# pcb_telemetria_wide.net
KiCad netlist of a schematic drawn in EAGLE
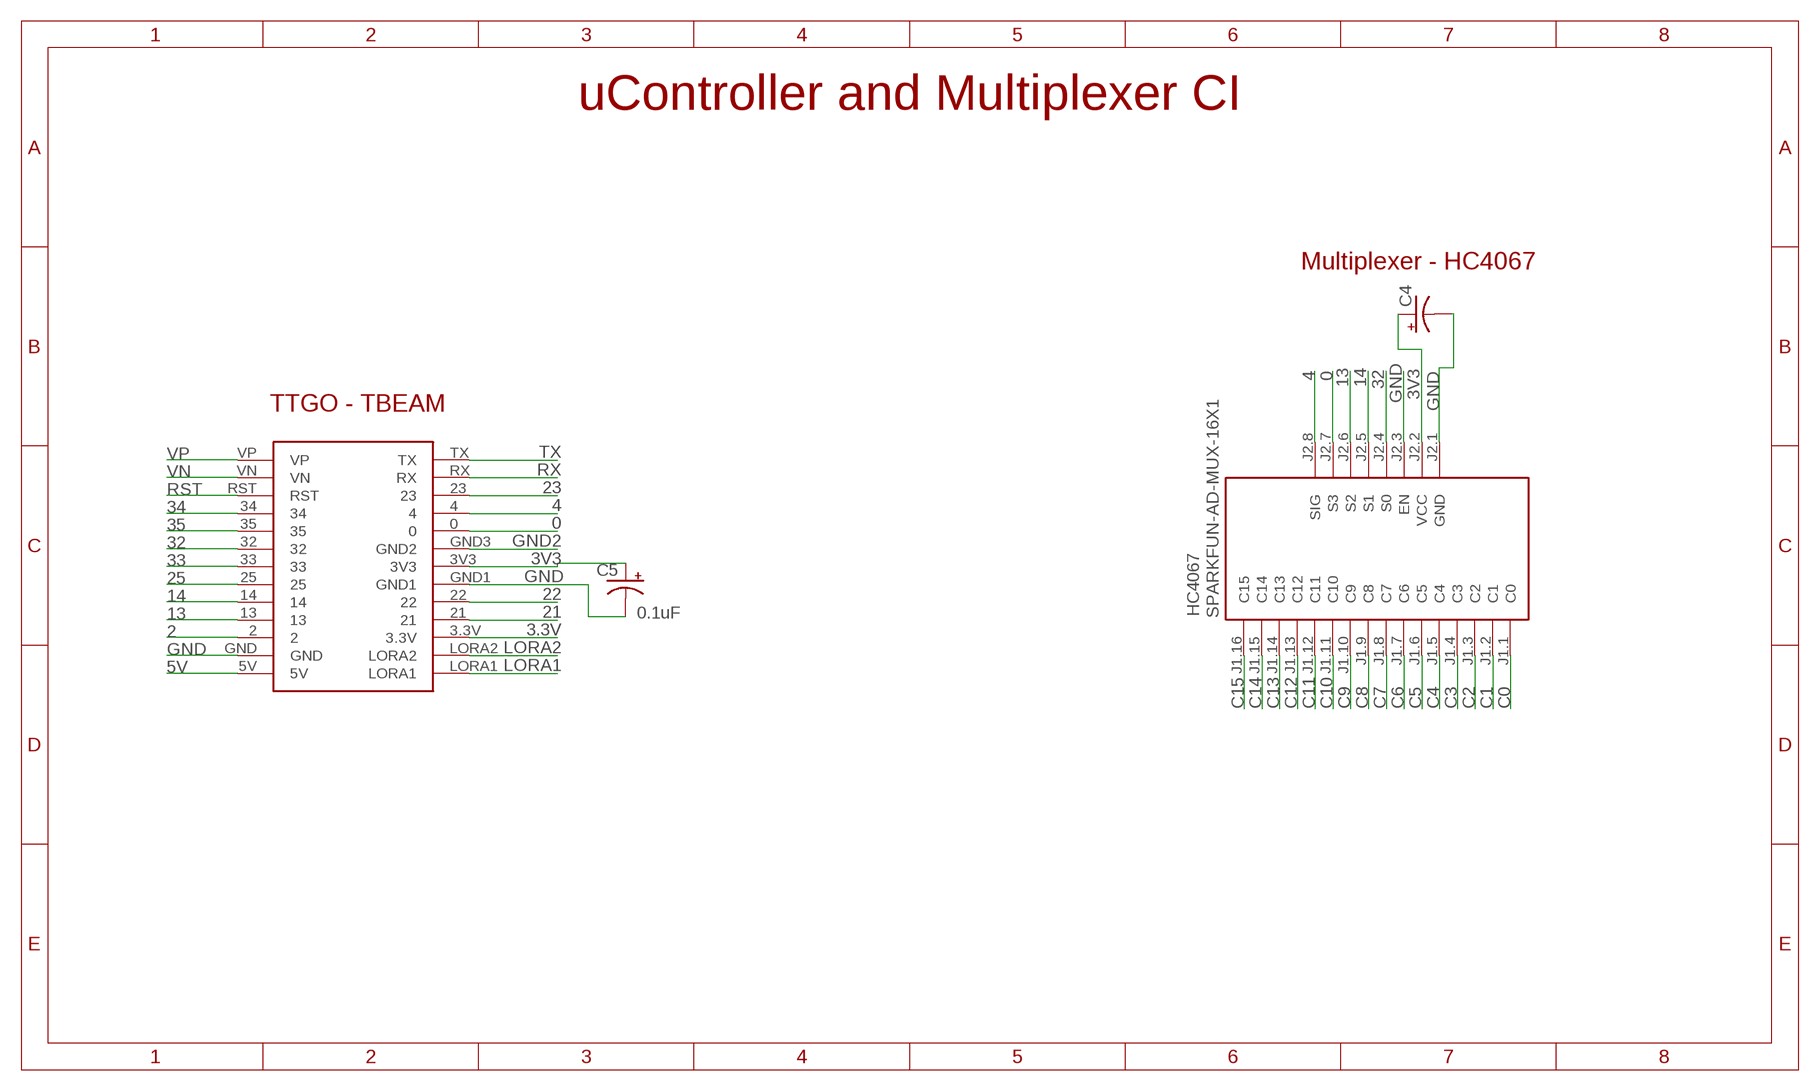
[diagram p0: schematic, sheet 1]
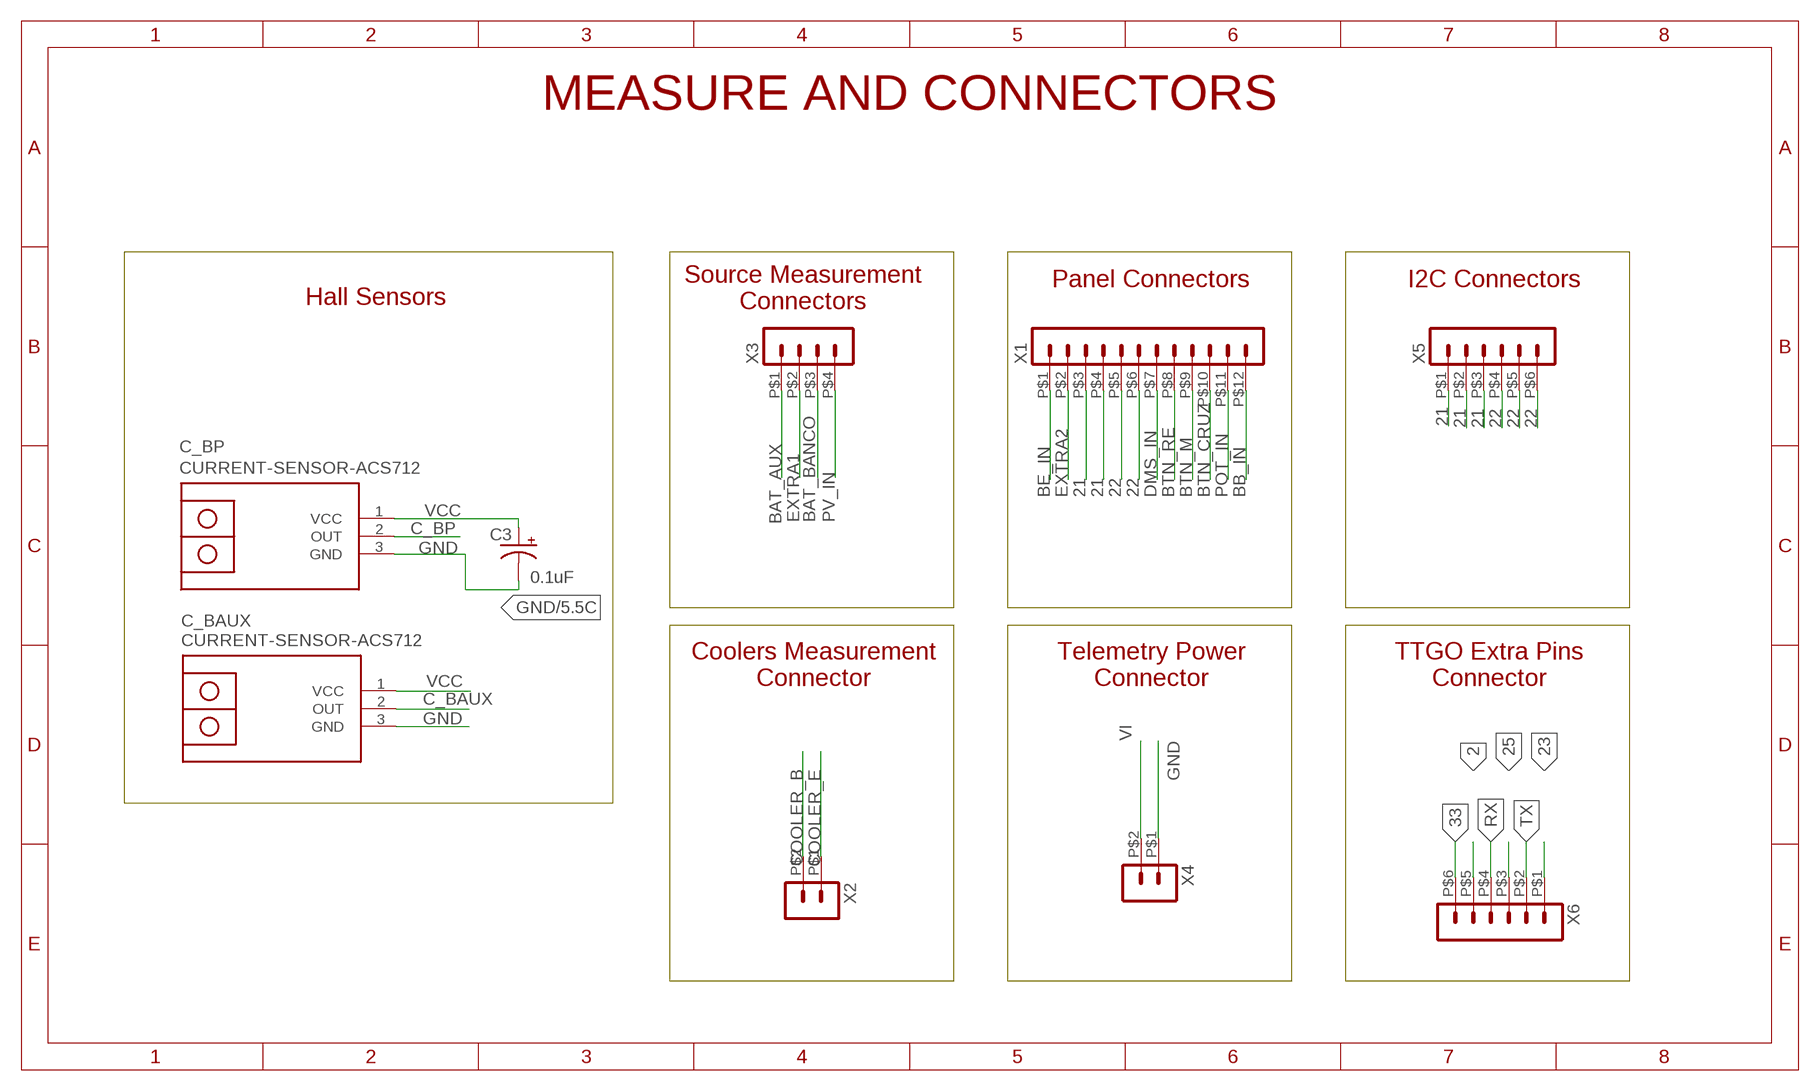
[diagram p1: schematic, sheet 2]
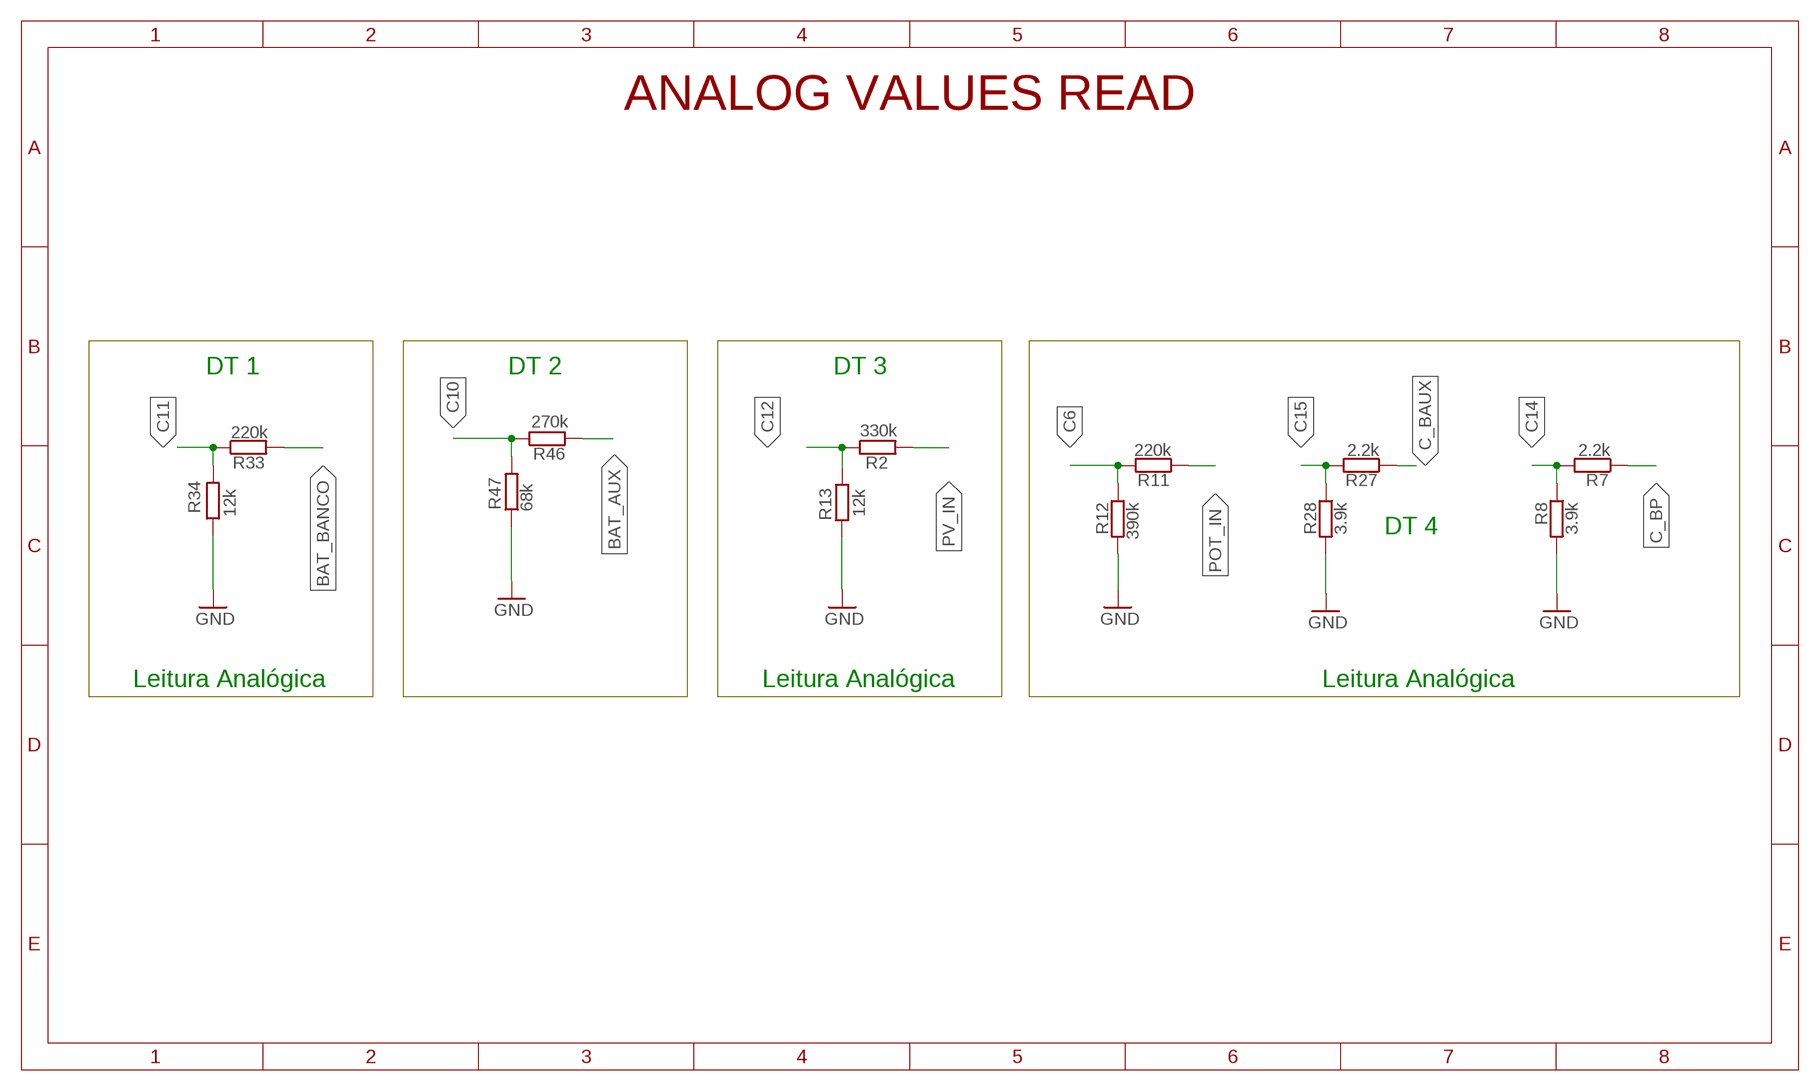
[diagram p2: schematic, sheet 3]
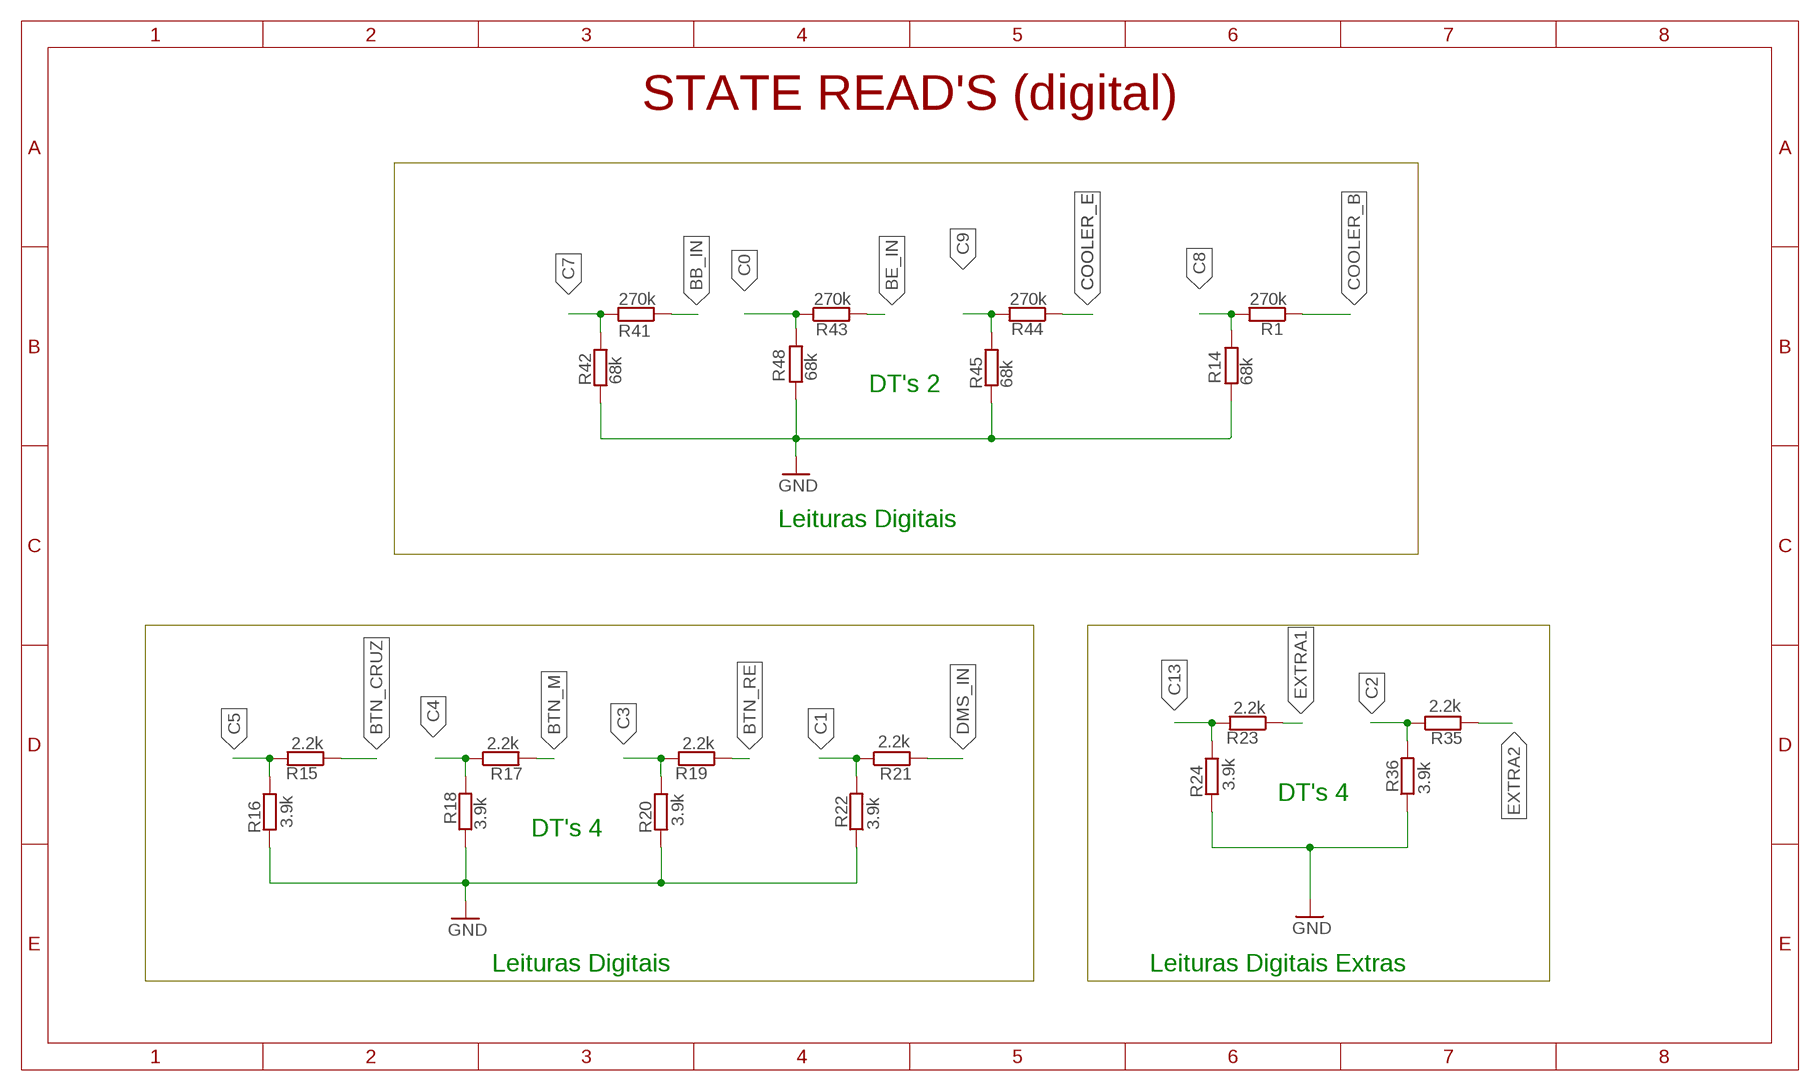
[diagram p3: schematic, sheet 4]
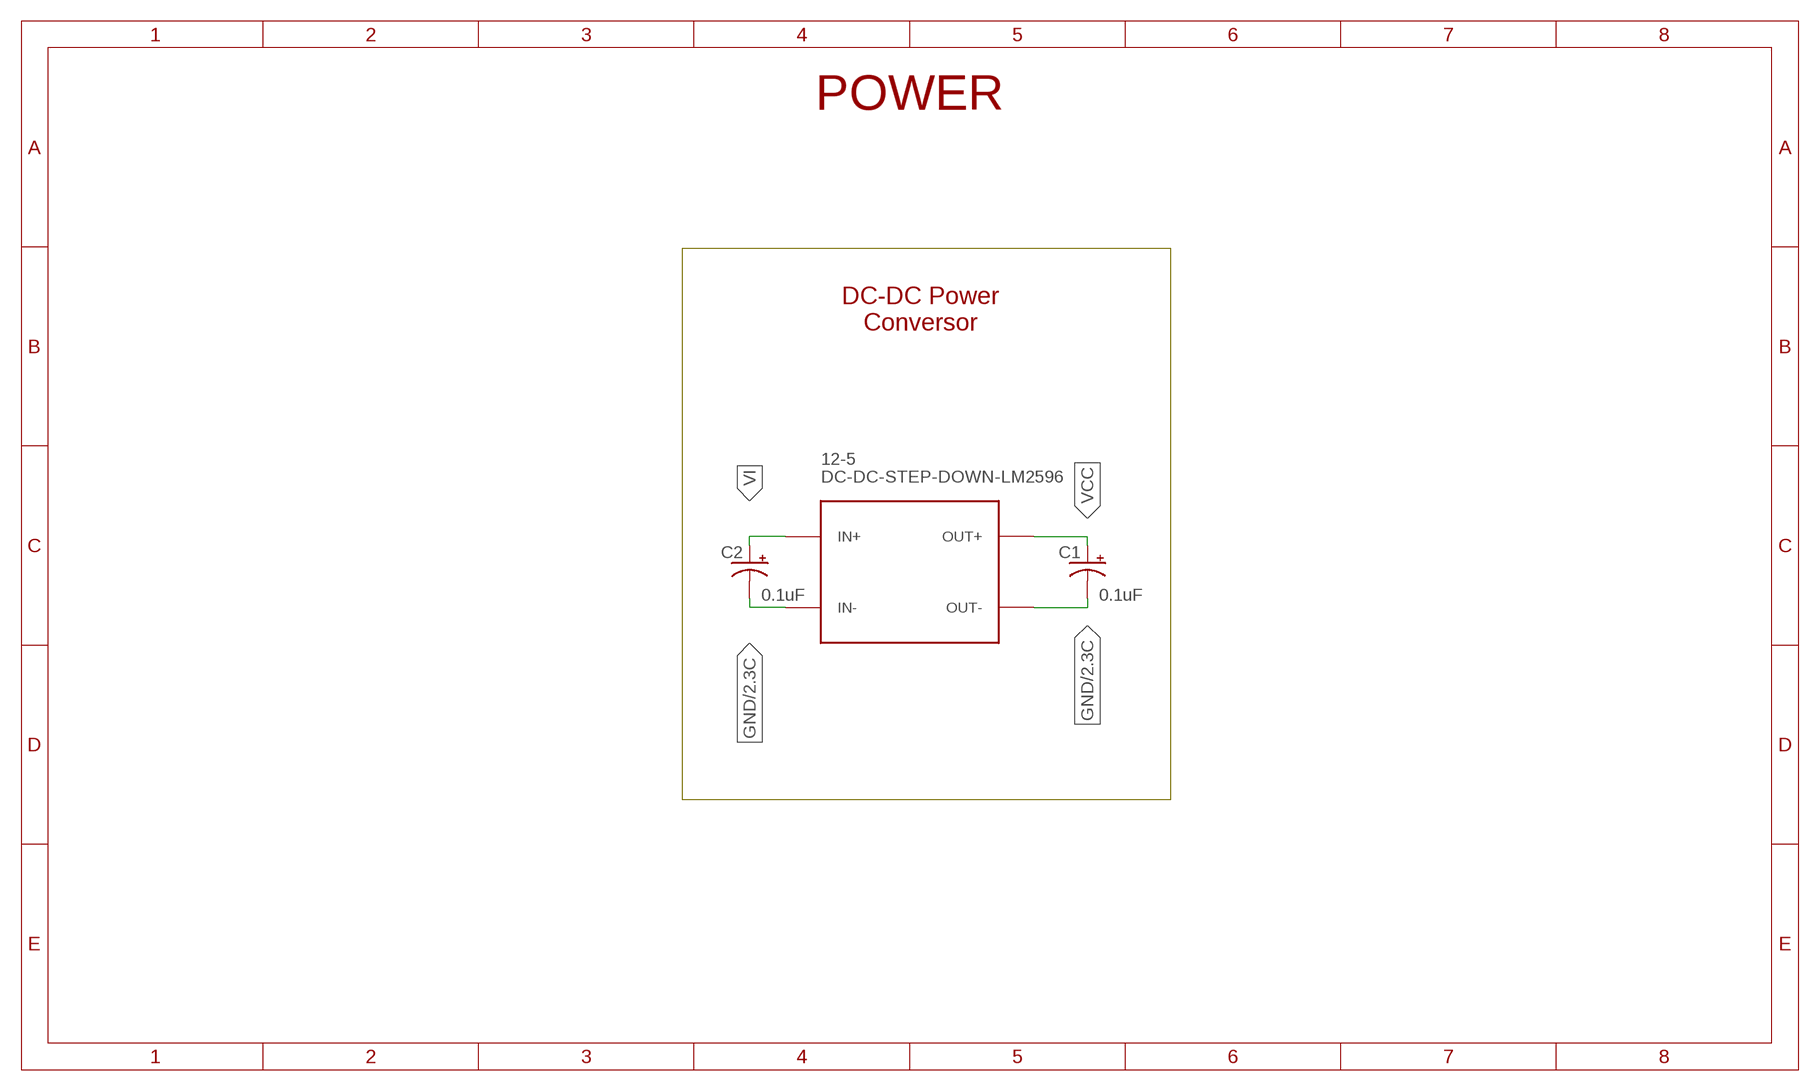
[diagram p4: schematic, sheet 5]

(export (version "E")
  (design (tool "Eeschema 10.0.6"))
  (components
    (comp (ref "12-5")
      (value "DC-DC-STEP-DOWN-LM2596")
      (footprint "eagle-import:DC-DC-STEP-DOWN-LM2596")
      (libsource (lib "eagle-import") (part "DC-DC-STEP-DOWN-LM2596"))
    )
    (comp (ref "C1")
      (value "0.1uF")
      (footprint "eagle-import:E5-5")
      (libsource (lib "eagle-import") (part "CPOL-USE5-5"))
    )
    (comp (ref "C2")
      (value "0.1uF")
      (footprint "eagle-import:E5-5")
      (libsource (lib "eagle-import") (part "CPOL-USE5-5"))
    )
    (comp (ref "R1")
      (value "270k")
      (footprint "eagle-import:0204_7")
      (libsource (lib "eagle-import") (part "R-EU_0204/7"))
    )
    (comp (ref "R14")
      (value "68k")
      (footprint "eagle-import:0204_7")
      (libsource (lib "eagle-import") (part "R-EU_0204/7"))
    )
    (comp (ref "R15")
      (value "2.2k")
      (footprint "eagle-import:0204_7")
      (libsource (lib "eagle-import") (part "R-EU_0204/7"))
    )
    (comp (ref "R16")
      (value "3.9k")
      (footprint "eagle-import:0204_7")
      (libsource (lib "eagle-import") (part "R-EU_0204/7"))
    )
    (comp (ref "R17")
      (value "2.2k")
      (footprint "eagle-import:0204_7")
      (libsource (lib "eagle-import") (part "R-EU_0204/7"))
    )
    (comp (ref "R18")
      (value "3.9k")
      (footprint "eagle-import:0204_7")
      (libsource (lib "eagle-import") (part "R-EU_0204/7"))
    )
    (comp (ref "R19")
      (value "2.2k")
      (footprint "eagle-import:0204_7")
      (libsource (lib "eagle-import") (part "R-EU_0204/7"))
    )
    (comp (ref "R20")
      (value "3.9k")
      (footprint "eagle-import:0204_7")
      (libsource (lib "eagle-import") (part "R-EU_0204/7"))
    )
    (comp (ref "R21")
      (value "2.2k")
      (footprint "eagle-import:0204_7")
      (libsource (lib "eagle-import") (part "R-EU_0204/7"))
    )
    (comp (ref "R22")
      (value "3.9k")
      (footprint "eagle-import:0204_7")
      (libsource (lib "eagle-import") (part "R-EU_0204/7"))
    )
    (comp (ref "R23")
      (value "2.2k")
      (footprint "eagle-import:0204_7")
      (libsource (lib "eagle-import") (part "R-EU_0204/7"))
    )
    (comp (ref "R24")
      (value "3.9k")
      (footprint "eagle-import:0204_7")
      (libsource (lib "eagle-import") (part "R-EU_0204/7"))
    )
    (comp (ref "R35")
      (value "2.2k")
      (footprint "eagle-import:0204_7")
      (libsource (lib "eagle-import") (part "R-EU_0204/7"))
    )
    (comp (ref "R36")
      (value "3.9k")
      (footprint "eagle-import:0204_7")
      (libsource (lib "eagle-import") (part "R-EU_0204/7"))
    )
    (comp (ref "R41")
      (value "270k")
      (footprint "eagle-import:0204_7")
      (libsource (lib "eagle-import") (part "R-EU_0204/7"))
    )
    (comp (ref "R42")
      (value "68k")
      (footprint "eagle-import:0204_7")
      (libsource (lib "eagle-import") (part "R-EU_0204/7"))
    )
    (comp (ref "R43")
      (value "270k")
      (footprint "eagle-import:0204_7")
      (libsource (lib "eagle-import") (part "R-EU_0204/7"))
    )
    (comp (ref "R44")
      (value "270k")
      (footprint "eagle-import:0204_7")
      (libsource (lib "eagle-import") (part "R-EU_0204/7"))
    )
    (comp (ref "R45")
      (value "68k")
      (footprint "eagle-import:0204_7")
      (libsource (lib "eagle-import") (part "R-EU_0204/7"))
    )
    (comp (ref "R48")
      (value "68k")
      (footprint "eagle-import:0204_7")
      (libsource (lib "eagle-import") (part "R-EU_0204/7"))
    )
    (comp (ref "C4")
      (value "CPOL-USE5-5")
      (footprint "eagle-import:E5-5")
      (libsource (lib "eagle-import") (part "CPOL-USE5-5"))
    )
    (comp (ref "C5")
      (value "0.1uF")
      (footprint "eagle-import:E5-5")
      (libsource (lib "eagle-import") (part "CPOL-USE5-5"))
    )
    (comp (ref "HC4067")
      (value "SPARKFUN-AD-MUX-16X1")
      (footprint "eagle-import:SPARKFUN-AD-MUX-16X1")
      (libsource (lib "eagle-import") (part "SPARKFUN-AD-MUX-16X1"))
    )
    (comp (ref "U$1")
      (value "TTGOBEAM")
      (footprint "eagle-import:TTGOBEAM")
      (libsource (lib "eagle-import") (part "TTGOBEAM"))
    )
    (comp (ref "R2")
      (value "330k")
      (footprint "eagle-import:0204_7")
      (libsource (lib "eagle-import") (part "R-EU_0204/7"))
    )
    (comp (ref "R7")
      (value "2.2k")
      (footprint "eagle-import:0204_7")
      (libsource (lib "eagle-import") (part "R-EU_0204/7"))
    )
    (comp (ref "R8")
      (value "3.9k")
      (footprint "eagle-import:0204_7")
      (libsource (lib "eagle-import") (part "R-EU_0204/7"))
    )
    (comp (ref "R11")
      (value "220k")
      (footprint "eagle-import:0204_7")
      (libsource (lib "eagle-import") (part "R-EU_0204/7"))
    )
    (comp (ref "R12")
      (value "390k")
      (footprint "eagle-import:0204_7")
      (libsource (lib "eagle-import") (part "R-EU_0204/7"))
    )
    (comp (ref "R13")
      (value "12k")
      (footprint "eagle-import:0204_7")
      (libsource (lib "eagle-import") (part "R-EU_0204/7"))
    )
    (comp (ref "R27")
      (value "2.2k")
      (footprint "eagle-import:0204_7")
      (libsource (lib "eagle-import") (part "R-EU_0204/7"))
    )
    (comp (ref "R28")
      (value "3.9k")
      (footprint "eagle-import:0204_7")
      (libsource (lib "eagle-import") (part "R-EU_0204/7"))
    )
    (comp (ref "R33")
      (value "220k")
      (footprint "eagle-import:0204_7")
      (libsource (lib "eagle-import") (part "R-EU_0204/7"))
    )
    (comp (ref "R34")
      (value "12k")
      (footprint "eagle-import:0204_7")
      (libsource (lib "eagle-import") (part "R-EU_0204/7"))
    )
    (comp (ref "R46")
      (value "270k")
      (footprint "eagle-import:0204_7")
      (libsource (lib "eagle-import") (part "R-EU_0204/7"))
    )
    (comp (ref "R47")
      (value "68k")
      (footprint "eagle-import:0204_7")
      (libsource (lib "eagle-import") (part "R-EU_0204/7"))
    )
    (comp (ref "C3")
      (value "0.1uF")
      (footprint "eagle-import:E5-5")
      (libsource (lib "eagle-import") (part "CPOL-USE5-5"))
    )
    (comp (ref "C_BAUX")
      (value "CURRENT-SENSOR-ACS712")
      (footprint "eagle-import:CURRENT-SENSOR-ACS712")
      (libsource (lib "eagle-import") (part "CURRENT-SENSOR-ACS712"))
    )
    (comp (ref "C_BP")
      (value "CURRENT-SENSOR-ACS712")
      (footprint "eagle-import:CURRENT-SENSOR-ACS712")
      (libsource (lib "eagle-import") (part "CURRENT-SENSOR-ACS712"))
    )
    (comp (ref "X1")
      (value "HEADER_POS12_43045-1212")
      (footprint "eagle-import:43045-1212")
      (libsource (lib "eagle-import") (part "HEADER_POS12_?43045-1212"))
    )
    (comp (ref "X2")
      (value "HEADER_POS2_43045-0212")
      (footprint "eagle-import:43045-0212")
      (libsource (lib "eagle-import") (part "HEADER_POS2_?43045-0212"))
    )
    (comp (ref "X3")
      (value "HEADER_POS4_43045-0412")
      (footprint "eagle-import:43045-0412")
      (libsource (lib "eagle-import") (part "HEADER_POS4_?43045-0412"))
    )
    (comp (ref "X4")
      (value "HEADER_POS2_43045-0212")
      (footprint "eagle-import:43045-0212")
      (libsource (lib "eagle-import") (part "HEADER_POS2_?43045-0212"))
    )
    (comp (ref "X5")
      (value "HEADER_POS6_43045-0612")
      (footprint "eagle-import:43045-0612")
      (libsource (lib "eagle-import") (part "HEADER_POS6_?43045-0612"))
    )
    (comp (ref "X6")
      (value "HEADER_POS6_43045-0612")
      (footprint "eagle-import:43045-0612")
      (libsource (lib "eagle-import") (part "HEADER_POS6_?43045-0612"))
    )
  )
  (nets
    (net (code "1") (name "0") (class "Default")
      (node (ref "HC4067") (pin "J2.7") (pinfunction "S3_J2.7") (pintype "bidirectional"))
      (node (ref "U$1") (pin "0") (pinfunction "0_0") (pintype "bidirectional"))
    )
    (net (code "2") (name "2") (class "Default")
      (node (ref "U$1") (pin "2") (pinfunction "2_2") (pintype "bidirectional"))
      (node (ref "X6") (pin "P$5") (pinfunction "5_P$5") (pintype "passive"))
    )
    (net (code "3") (name "3.3V") (class "Default")
      (node (ref "U$1") (pin "3.3V") (pinfunction "3.3V_3.3V") (pintype "bidirectional"))
    )
    (net (code "4") (name "3V3") (class "Default")
      (node (ref "C4") (pin "+") (pinfunction "+_+") (pintype "passive"))
      (node (ref "C5") (pin "+") (pinfunction "+_+") (pintype "passive"))
      (node (ref "HC4067") (pin "J2.2") (pinfunction "VCC_J2.2") (pintype "power_in"))
      (node (ref "U$1") (pin "3V3") (pinfunction "3V3_3V3") (pintype "bidirectional"))
    )
    (net (code "5") (name "4") (class "Default")
      (node (ref "HC4067") (pin "J2.8") (pinfunction "SIG_J2.8") (pintype "bidirectional"))
      (node (ref "U$1") (pin "4") (pinfunction "4_4") (pintype "bidirectional"))
    )
    (net (code "6") (name "5V") (class "Default")
      (node (ref "U$1") (pin "5V") (pinfunction "5V_5V") (pintype "bidirectional"))
    )
    (net (code "7") (name "13") (class "Default")
      (node (ref "HC4067") (pin "J2.6") (pinfunction "S2_J2.6") (pintype "bidirectional"))
      (node (ref "U$1") (pin "13") (pinfunction "13_13") (pintype "bidirectional"))
    )
    (net (code "8") (name "14") (class "Default")
      (node (ref "HC4067") (pin "J2.5") (pinfunction "S1_J2.5") (pintype "bidirectional"))
      (node (ref "U$1") (pin "14") (pinfunction "14_14") (pintype "bidirectional"))
    )
    (net (code "9") (name "21") (class "Default")
      (node (ref "U$1") (pin "21") (pinfunction "21_21") (pintype "bidirectional"))
      (node (ref "X1") (pin "P$3") (pinfunction "3_P$3") (pintype "passive"))
      (node (ref "X1") (pin "P$4") (pinfunction "4_P$4") (pintype "passive"))
      (node (ref "X5") (pin "P$1") (pinfunction "1_P$1") (pintype "passive"))
      (node (ref "X5") (pin "P$2") (pinfunction "2_P$2") (pintype "passive"))
      (node (ref "X5") (pin "P$3") (pinfunction "3_P$3") (pintype "passive"))
    )
    (net (code "10") (name "22") (class "Default")
      (node (ref "U$1") (pin "22") (pinfunction "22_22") (pintype "bidirectional"))
      (node (ref "X1") (pin "P$5") (pinfunction "5_P$5") (pintype "passive"))
      (node (ref "X1") (pin "P$6") (pinfunction "6_P$6") (pintype "passive"))
      (node (ref "X5") (pin "P$4") (pinfunction "4_P$4") (pintype "passive"))
      (node (ref "X5") (pin "P$5") (pinfunction "5_P$5") (pintype "passive"))
      (node (ref "X5") (pin "P$6") (pinfunction "6_P$6") (pintype "passive"))
    )
    (net (code "11") (name "23") (class "Default")
      (node (ref "U$1") (pin "23") (pinfunction "23_23") (pintype "bidirectional"))
      (node (ref "X6") (pin "P$1") (pinfunction "1_P$1") (pintype "passive"))
    )
    (net (code "12") (name "25") (class "Default")
      (node (ref "U$1") (pin "25") (pinfunction "25_25") (pintype "bidirectional"))
      (node (ref "X6") (pin "P$3") (pinfunction "3_P$3") (pintype "passive"))
    )
    (net (code "13") (name "32") (class "Default")
      (node (ref "HC4067") (pin "J2.4") (pinfunction "S0_J2.4") (pintype "bidirectional"))
      (node (ref "U$1") (pin "32") (pinfunction "32_32") (pintype "bidirectional"))
    )
    (net (code "14") (name "33") (class "Default")
      (node (ref "U$1") (pin "33") (pinfunction "33_33") (pintype "bidirectional"))
      (node (ref "X6") (pin "P$6") (pinfunction "6_P$6") (pintype "passive"))
    )
    (net (code "15") (name "34") (class "Default")
      (node (ref "U$1") (pin "34") (pinfunction "34_34") (pintype "bidirectional"))
    )
    (net (code "16") (name "35") (class "Default")
      (node (ref "U$1") (pin "35") (pinfunction "35_35") (pintype "bidirectional"))
    )
    (net (code "17") (name "BAT_AUX") (class "Default")
      (node (ref "R46") (pin "2") (pinfunction "2_2") (pintype "passive"))
      (node (ref "X3") (pin "P$1") (pinfunction "1_P$1") (pintype "passive"))
    )
    (net (code "18") (name "BAT_BANCO") (class "Default")
      (node (ref "R33") (pin "2") (pinfunction "2_2") (pintype "passive"))
      (node (ref "X3") (pin "P$3") (pinfunction "3_P$3") (pintype "passive"))
    )
    (net (code "19") (name "BB_IN") (class "Default")
      (node (ref "R41") (pin "1") (pinfunction "1_1") (pintype "passive"))
      (node (ref "X1") (pin "P$12") (pinfunction "12_P$12") (pintype "passive"))
    )
    (net (code "20") (name "BE_IN") (class "Default")
      (node (ref "R43") (pin "2") (pinfunction "2_2") (pintype "passive"))
      (node (ref "X1") (pin "P$1") (pinfunction "1_P$1") (pintype "passive"))
    )
    (net (code "21") (name "BTN_CRUZ") (class "Default")
      (node (ref "R15") (pin "1") (pinfunction "1_1") (pintype "passive"))
      (node (ref "X1") (pin "P$10") (pinfunction "10_P$10") (pintype "passive"))
    )
    (net (code "22") (name "BTN_M") (class "Default")
      (node (ref "R17") (pin "2") (pinfunction "2_2") (pintype "passive"))
      (node (ref "X1") (pin "P$9") (pinfunction "9_P$9") (pintype "passive"))
    )
    (net (code "23") (name "BTN_RE") (class "Default")
      (node (ref "R19") (pin "1") (pinfunction "1_1") (pintype "passive"))
      (node (ref "X1") (pin "P$8") (pinfunction "8_P$8") (pintype "passive"))
    )
    (net (code "24") (name "C0") (class "Default")
      (node (ref "HC4067") (pin "J1.1") (pinfunction "C0_J1.1") (pintype "bidirectional"))
      (node (ref "R43") (pin "1") (pinfunction "1_1") (pintype "passive"))
      (node (ref "R48") (pin "1") (pinfunction "1_1") (pintype "passive"))
    )
    (net (code "25") (name "C1") (class "Default")
      (node (ref "HC4067") (pin "J1.2") (pinfunction "C1_J1.2") (pintype "bidirectional"))
      (node (ref "R21") (pin "1") (pinfunction "1_1") (pintype "passive"))
      (node (ref "R22") (pin "2") (pinfunction "2_2") (pintype "passive"))
    )
    (net (code "26") (name "C2") (class "Default")
      (node (ref "HC4067") (pin "J1.3") (pinfunction "C2_J1.3") (pintype "bidirectional"))
      (node (ref "R35") (pin "1") (pinfunction "1_1") (pintype "passive"))
      (node (ref "R36") (pin "2") (pinfunction "2_2") (pintype "passive"))
    )
    (net (code "27") (name "C3") (class "Default")
      (node (ref "HC4067") (pin "J1.4") (pinfunction "C3_J1.4") (pintype "bidirectional"))
      (node (ref "R19") (pin "2") (pinfunction "2_2") (pintype "passive"))
      (node (ref "R20") (pin "1") (pinfunction "1_1") (pintype "passive"))
    )
    (net (code "28") (name "C4") (class "Default")
      (node (ref "HC4067") (pin "J1.5") (pinfunction "C4_J1.5") (pintype "bidirectional"))
      (node (ref "R17") (pin "1") (pinfunction "1_1") (pintype "passive"))
      (node (ref "R18") (pin "2") (pinfunction "2_2") (pintype "passive"))
    )
    (net (code "29") (name "C5") (class "Default")
      (node (ref "HC4067") (pin "J1.6") (pinfunction "C5_J1.6") (pintype "bidirectional"))
      (node (ref "R15") (pin "2") (pinfunction "2_2") (pintype "passive"))
      (node (ref "R16") (pin "1") (pinfunction "1_1") (pintype "passive"))
    )
    (net (code "30") (name "C6") (class "Default")
      (node (ref "HC4067") (pin "J1.7") (pinfunction "C6_J1.7") (pintype "bidirectional"))
      (node (ref "R11") (pin "2") (pinfunction "2_2") (pintype "passive"))
      (node (ref "R12") (pin "1") (pinfunction "1_1") (pintype "passive"))
    )
    (net (code "31") (name "C7") (class "Default")
      (node (ref "HC4067") (pin "J1.8") (pinfunction "C7_J1.8") (pintype "bidirectional"))
      (node (ref "R41") (pin "2") (pinfunction "2_2") (pintype "passive"))
      (node (ref "R42") (pin "1") (pinfunction "1_1") (pintype "passive"))
    )
    (net (code "32") (name "C8") (class "Default")
      (node (ref "HC4067") (pin "J1.9") (pinfunction "C8_J1.9") (pintype "bidirectional"))
      (node (ref "R1") (pin "2") (pinfunction "2_2") (pintype "passive"))
      (node (ref "R14") (pin "2") (pinfunction "2_2") (pintype "passive"))
    )
    (net (code "33") (name "C9") (class "Default")
      (node (ref "HC4067") (pin "J1.10") (pinfunction "C9_J1.10") (pintype "bidirectional"))
      (node (ref "R44") (pin "2") (pinfunction "2_2") (pintype "passive"))
      (node (ref "R45") (pin "1") (pinfunction "1_1") (pintype "passive"))
    )
    (net (code "34") (name "C10") (class "Default")
      (node (ref "HC4067") (pin "J1.11") (pinfunction "C10_J1.11") (pintype "bidirectional"))
      (node (ref "R46") (pin "1") (pinfunction "1_1") (pintype "passive"))
      (node (ref "R47") (pin "2") (pinfunction "2_2") (pintype "passive"))
    )
    (net (code "35") (name "C11") (class "Default")
      (node (ref "HC4067") (pin "J1.12") (pinfunction "C11_J1.12") (pintype "bidirectional"))
      (node (ref "R33") (pin "1") (pinfunction "1_1") (pintype "passive"))
      (node (ref "R34") (pin "2") (pinfunction "2_2") (pintype "passive"))
    )
    (net (code "36") (name "C12") (class "Default")
      (node (ref "HC4067") (pin "J1.13") (pinfunction "C12_J1.13") (pintype "bidirectional"))
      (node (ref "R13") (pin "2") (pinfunction "2_2") (pintype "passive"))
      (node (ref "R2") (pin "1") (pinfunction "1_1") (pintype "passive"))
    )
    (net (code "37") (name "C13") (class "Default")
      (node (ref "HC4067") (pin "J1.14") (pinfunction "C13_J1.14") (pintype "bidirectional"))
      (node (ref "R23") (pin "2") (pinfunction "2_2") (pintype "passive"))
      (node (ref "R24") (pin "1") (pinfunction "1_1") (pintype "passive"))
    )
    (net (code "38") (name "C14") (class "Default")
      (node (ref "HC4067") (pin "J1.15") (pinfunction "C14_J1.15") (pintype "bidirectional"))
      (node (ref "R7") (pin "2") (pinfunction "2_2") (pintype "passive"))
      (node (ref "R8") (pin "1") (pinfunction "1_1") (pintype "passive"))
    )
    (net (code "39") (name "C15") (class "Default")
      (node (ref "HC4067") (pin "J1.16") (pinfunction "C15_J1.16") (pintype "bidirectional"))
      (node (ref "R27") (pin "2") (pinfunction "2_2") (pintype "passive"))
      (node (ref "R28") (pin "1") (pinfunction "1_1") (pintype "passive"))
    )
    (net (code "40") (name "COOLER_B") (class "Default")
      (node (ref "R1") (pin "1") (pinfunction "1_1") (pintype "passive"))
      (node (ref "X2") (pin "P$2") (pinfunction "2_P$2") (pintype "passive"))
    )
    (net (code "41") (name "COOLER_E") (class "Default")
      (node (ref "R44") (pin "1") (pinfunction "1_1") (pintype "passive"))
      (node (ref "X2") (pin "P$1") (pinfunction "1_P$1") (pintype "passive"))
    )
    (net (code "42") (name "C_BAUX") (class "Default")
      (node (ref "C_BAUX") (pin "2") (pinfunction "OUT_2") (pintype "output"))
      (node (ref "R27") (pin "1") (pinfunction "1_1") (pintype "passive"))
    )
    (net (code "43") (name "C_BP") (class "Default")
      (node (ref "C_BP") (pin "2") (pinfunction "OUT_2") (pintype "output"))
      (node (ref "R7") (pin "1") (pinfunction "1_1") (pintype "passive"))
    )
    (net (code "44") (name "DMS_IN") (class "Default")
      (node (ref "R21") (pin "2") (pinfunction "2_2") (pintype "passive"))
      (node (ref "X1") (pin "P$7") (pinfunction "7_P$7") (pintype "passive"))
    )
    (net (code "45") (name "EXTRA1") (class "Default")
      (node (ref "R23") (pin "1") (pinfunction "1_1") (pintype "passive"))
      (node (ref "X3") (pin "P$2") (pinfunction "2_P$2") (pintype "passive"))
    )
    (net (code "46") (name "EXTRA2") (class "Default")
      (node (ref "R35") (pin "2") (pinfunction "2_2") (pintype "passive"))
      (node (ref "X1") (pin "P$2") (pinfunction "2_P$2") (pintype "passive"))
    )
    (net (code "47") (name "GND") (class "Default")
      (node (ref "12-5") (pin "IN-") (pinfunction "IN-_IN-") (pintype "bidirectional"))
      (node (ref "12-5") (pin "OUT-") (pinfunction "OUT-_OUT-") (pintype "bidirectional"))
      (node (ref "C1") (pin "-") (pinfunction "-_-") (pintype "passive"))
      (node (ref "C2") (pin "-") (pinfunction "-_-") (pintype "passive"))
      (node (ref "C3") (pin "-") (pinfunction "-_-") (pintype "passive"))
      (node (ref "C4") (pin "-") (pinfunction "-_-") (pintype "passive"))
      (node (ref "C5") (pin "-") (pinfunction "-_-") (pintype "passive"))
      (node (ref "C_BAUX") (pin "3") (pinfunction "GND_3") (pintype "power_in"))
      (node (ref "C_BP") (pin "3") (pinfunction "GND_3") (pintype "power_in"))
      (node (ref "HC4067") (pin "J2.1") (pinfunction "GND_J2.1") (pintype "power_in"))
      (node (ref "HC4067") (pin "J2.3") (pinfunction "EN_J2.3") (pintype "input"))
      (node (ref "R12") (pin "2") (pinfunction "2_2") (pintype "passive"))
      (node (ref "R13") (pin "1") (pinfunction "1_1") (pintype "passive"))
      (node (ref "R14") (pin "1") (pinfunction "1_1") (pintype "passive"))
      (node (ref "R16") (pin "2") (pinfunction "2_2") (pintype "passive"))
      (node (ref "R18") (pin "1") (pinfunction "1_1") (pintype "passive"))
      (node (ref "R20") (pin "2") (pinfunction "2_2") (pintype "passive"))
      (node (ref "R22") (pin "1") (pinfunction "1_1") (pintype "passive"))
      (node (ref "R24") (pin "2") (pinfunction "2_2") (pintype "passive"))
      (node (ref "R28") (pin "2") (pinfunction "2_2") (pintype "passive"))
      (node (ref "R34") (pin "1") (pinfunction "1_1") (pintype "passive"))
      (node (ref "R36") (pin "1") (pinfunction "1_1") (pintype "passive"))
      (node (ref "R42") (pin "2") (pinfunction "2_2") (pintype "passive"))
      (node (ref "R45") (pin "2") (pinfunction "2_2") (pintype "passive"))
      (node (ref "R47") (pin "1") (pinfunction "1_1") (pintype "passive"))
      (node (ref "R48") (pin "2") (pinfunction "2_2") (pintype "passive"))
      (node (ref "R8") (pin "2") (pinfunction "2_2") (pintype "passive"))
      (node (ref "U$1") (pin "GND") (pinfunction "GND_GND") (pintype "bidirectional"))
      (node (ref "U$1") (pin "GND1") (pinfunction "GND1_GND1") (pintype "bidirectional"))
      (node (ref "X4") (pin "P$1") (pinfunction "1_P$1") (pintype "passive"))
    )
    (net (code "48") (name "GND2") (class "Default")
      (node (ref "U$1") (pin "GND3") (pinfunction "GND2_GND3") (pintype "bidirectional"))
    )
    (net (code "49") (name "LORA1") (class "Default")
      (node (ref "U$1") (pin "LORA1") (pinfunction "LORA1_LORA1") (pintype "bidirectional"))
    )
    (net (code "50") (name "LORA2") (class "Default")
      (node (ref "U$1") (pin "LORA2") (pinfunction "LORA2_LORA2") (pintype "bidirectional"))
    )
    (net (code "51") (name "POT_IN") (class "Default")
      (node (ref "R11") (pin "1") (pinfunction "1_1") (pintype "passive"))
      (node (ref "X1") (pin "P$11") (pinfunction "11_P$11") (pintype "passive"))
    )
    (net (code "52") (name "PV_IN") (class "Default")
      (node (ref "R2") (pin "2") (pinfunction "2_2") (pintype "passive"))
      (node (ref "X3") (pin "P$4") (pinfunction "4_P$4") (pintype "passive"))
    )
    (net (code "53") (name "RST") (class "Default")
      (node (ref "U$1") (pin "RST") (pinfunction "RST_RST") (pintype "bidirectional"))
    )
    (net (code "54") (name "RX") (class "Default")
      (node (ref "U$1") (pin "RX") (pinfunction "RX_RX") (pintype "bidirectional"))
      (node (ref "X6") (pin "P$4") (pinfunction "4_P$4") (pintype "passive"))
    )
    (net (code "55") (name "TX") (class "Default")
      (node (ref "U$1") (pin "TX") (pinfunction "TX_TX") (pintype "bidirectional"))
      (node (ref "X6") (pin "P$2") (pinfunction "2_P$2") (pintype "passive"))
    )
    (net (code "56") (name "VCC") (class "Default")
      (node (ref "12-5") (pin "OUT+") (pinfunction "OUT+_OUT+") (pintype "bidirectional"))
      (node (ref "C1") (pin "+") (pinfunction "+_+") (pintype "passive"))
      (node (ref "C3") (pin "+") (pinfunction "+_+") (pintype "passive"))
      (node (ref "C_BAUX") (pin "1") (pinfunction "VCC_1") (pintype "power_in"))
      (node (ref "C_BP") (pin "1") (pinfunction "VCC_1") (pintype "power_in"))
    )
    (net (code "57") (name "VI") (class "Default")
      (node (ref "12-5") (pin "IN+") (pinfunction "IN+_IN+") (pintype "bidirectional"))
      (node (ref "C2") (pin "+") (pinfunction "+_+") (pintype "passive"))
      (node (ref "X4") (pin "P$2") (pinfunction "2_P$2") (pintype "passive"))
    )
    (net (code "58") (name "VN") (class "Default")
      (node (ref "U$1") (pin "VN") (pinfunction "VN_VN") (pintype "bidirectional"))
    )
    (net (code "59") (name "VP") (class "Default")
      (node (ref "U$1") (pin "VP") (pinfunction "VP_VP") (pintype "bidirectional"))
    )
  )
)
